# mimic1568_DtoA.net
KiCad netlist of a schematic drawn in EAGLE
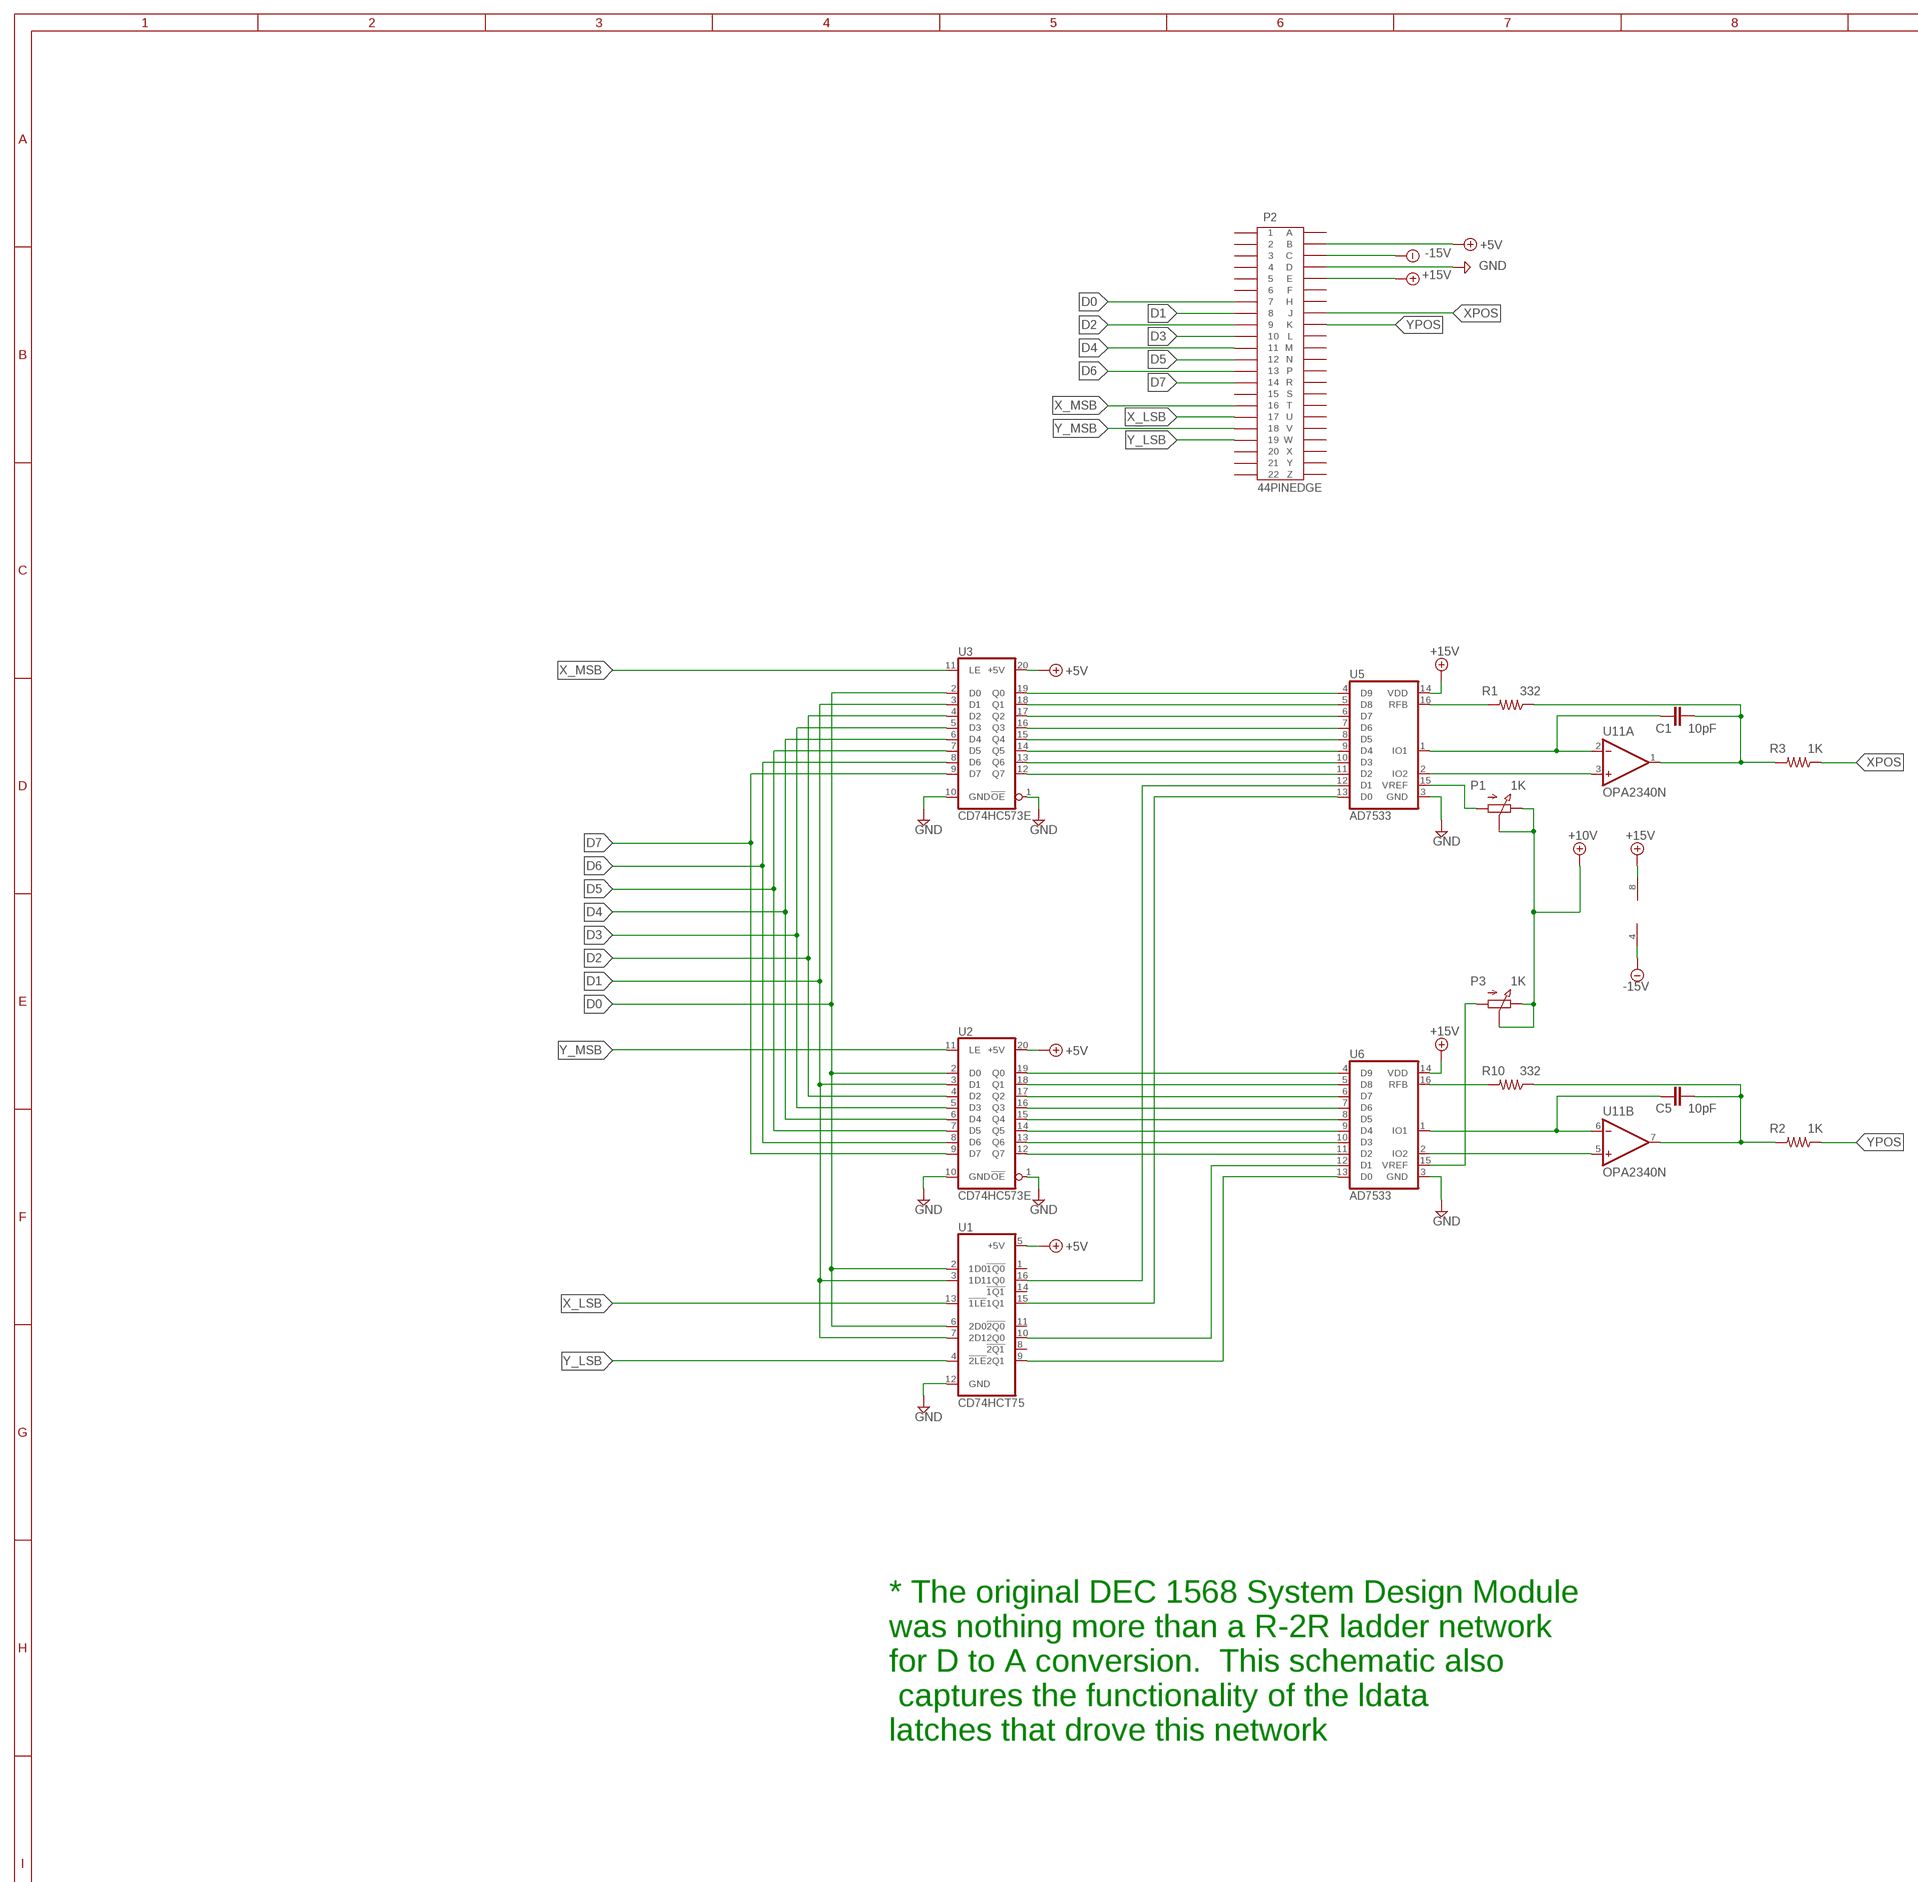
[diagram p0: schematic, sheet 1, part 1 of 2]
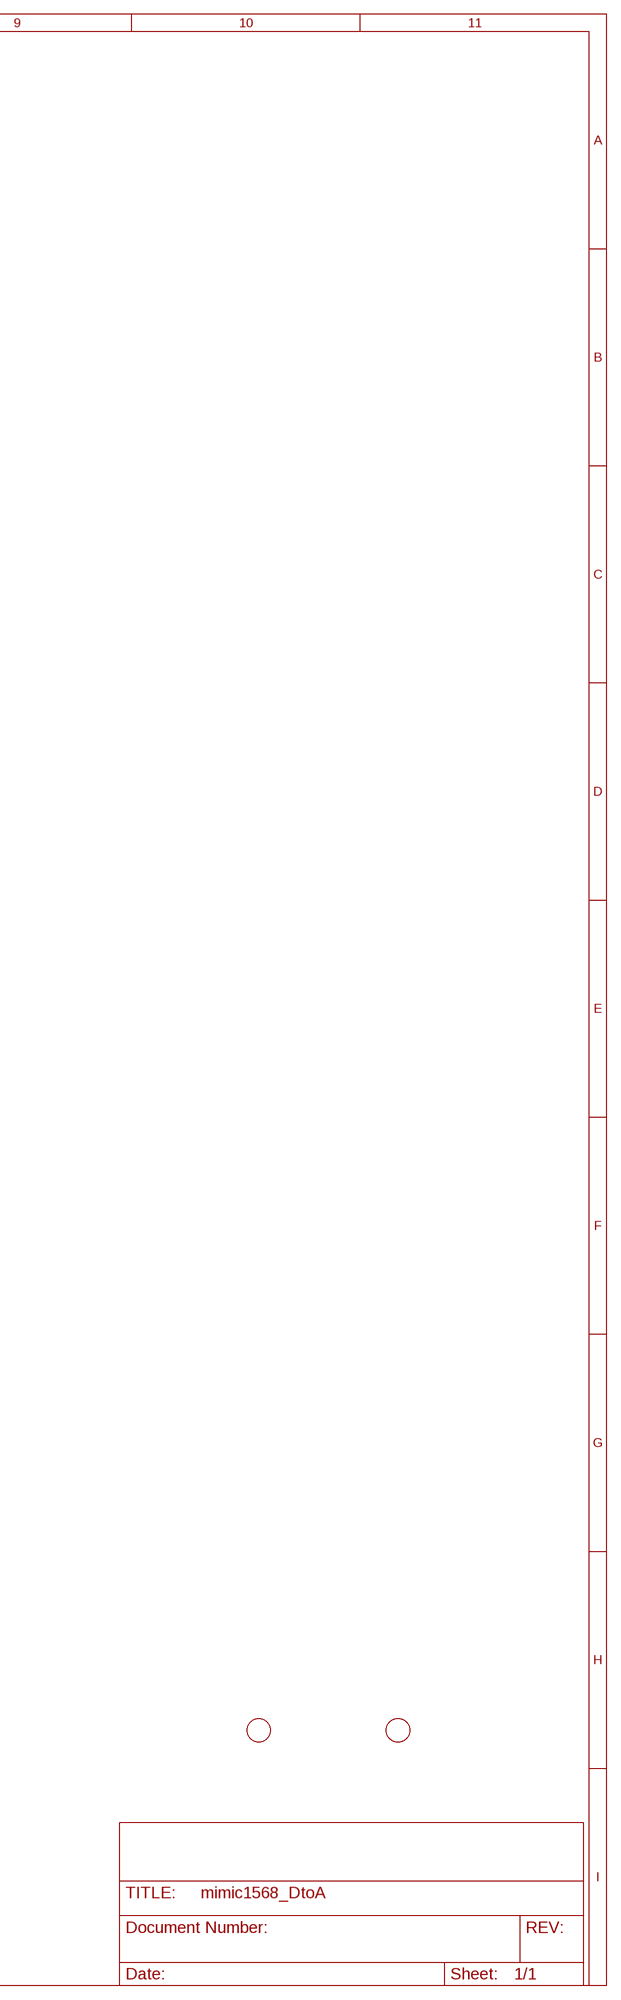
[diagram p1: schematic, sheet 1, part 2 of 2]

(export (version "E")
  (design (tool "Eeschema 10.0.6"))
  (components
    (comp (ref "C1")
      (value "10pF")
      (footprint "eagle-import:C2.5")
      (libsource (lib "eagle-import") (part "C-0.1"))
    )
    (comp (ref "C5")
      (value "10pF")
      (footprint "eagle-import:C2.5")
      (libsource (lib "eagle-import") (part "C-0.1"))
    )
    (comp (ref "P1")
      (value "1K")
      (footprint "eagle-import:3006P")
      (libsource (lib "eagle-import") (part "POT-3006P"))
    )
    (comp (ref "P2")
      (value "44PINEDGE")
      (footprint "eagle-import:44PINEDGE")
      (libsource (lib "eagle-import") (part "44PINEDGE"))
    )
    (comp (ref "P3")
      (value "1K")
      (footprint "eagle-import:3006P")
      (libsource (lib "eagle-import") (part "POT-3006P"))
    )
    (comp (ref "R1")
      (value "332")
      (footprint "eagle-import:0207_10")
      (libsource (lib "eagle-import") (part "R-1/4WATT"))
    )
    (comp (ref "R2")
      (value "1K")
      (footprint "eagle-import:0207_10")
      (libsource (lib "eagle-import") (part "R-1/4WATT"))
    )
    (comp (ref "R3")
      (value "1K")
      (footprint "eagle-import:0207_10")
      (libsource (lib "eagle-import") (part "R-1/4WATT"))
    )
    (comp (ref "R10")
      (value "332")
      (footprint "eagle-import:0207_10")
      (libsource (lib "eagle-import") (part "R-1/4WATT"))
    )
    (comp (ref "U$1")
      (value "FIDUCIAL")
      (footprint "eagle-import:FIDUCIAL_1MM")
      (libsource (lib "eagle-import") (part "FIDUCIAL"))
    )
    (comp (ref "U$2")
      (value "FIDUCIAL")
      (footprint "eagle-import:FIDUCIAL_1MM")
      (libsource (lib "eagle-import") (part "FIDUCIAL"))
    )
    (comp (ref "U1")
      (value "CD74HCT75")
      (footprint "eagle-import:DIP-16")
      (libsource (lib "eagle-import") (part "CD74HCT75"))
    )
    (comp (ref "U2")
      (value "CD74HC573E")
      (footprint "eagle-import:DIP-20")
      (libsource (lib "eagle-import") (part "CD74HC573E"))
    )
    (comp (ref "U3")
      (value "CD74HC573E")
      (footprint "eagle-import:DIP-20")
      (libsource (lib "eagle-import") (part "CD74HC573E"))
    )
    (comp (ref "U5")
      (value "AD7533")
      (footprint "eagle-import:DIP-16")
      (libsource (lib "eagle-import") (part "AD7533"))
    )
    (comp (ref "U6")
      (value "AD7533")
      (footprint "eagle-import:DIP-16")
      (libsource (lib "eagle-import") (part "AD7533"))
    )
    (comp (ref "U11")
      (value "OPA2340N")
      (footprint "eagle-import:DIP-08")
      (fields (field (name "PN") "OPA2340PA"))
      (libsource (lib "eagle-import") (part "OPA2340N"))
    )
  )
  (nets
    (net (code "1") (name "+5V") (class "Default")
      (node (ref "P2") (pin "B") (pinfunction "B_B") (pintype "passive"))
      (node (ref "U1") (pin "5") (pinfunction "+5V_5") (pintype "power_in"))
      (node (ref "U2") (pin "20") (pinfunction "+5V_20") (pintype "power_in"))
      (node (ref "U3") (pin "20") (pinfunction "+5V_20") (pintype "power_in"))
    )
    (net (code "2") (name "+10V") (class "Default")
      (node (ref "P1") (pin "2") (pinfunction "S_2") (pintype "passive"))
      (node (ref "P1") (pin "3") (pinfunction "E_3") (pintype "passive"))
      (node (ref "P3") (pin "2") (pinfunction "S_2") (pintype "passive"))
      (node (ref "P3") (pin "3") (pinfunction "E_3") (pintype "passive"))
    )
    (net (code "3") (name "+15V") (class "Default")
      (node (ref "P2") (pin "E") (pinfunction "E_E") (pintype "passive"))
      (node (ref "U11") (pin "8") (pinfunction "V+_8") (pintype "power_in"))
      (node (ref "U5") (pin "14") (pinfunction "VDD_14") (pintype "power_in"))
      (node (ref "U6") (pin "14") (pinfunction "VDD_14") (pintype "power_in"))
    )
    (net (code "4") (name "-15V") (class "Default")
      (node (ref "P2") (pin "C") (pinfunction "C_C") (pintype "passive"))
      (node (ref "U11") (pin "4") (pinfunction "V-_4") (pintype "power_in"))
    )
    (net (code "5") (name "D0") (class "Default")
      (node (ref "P2") (pin "7") (pinfunction "7_7") (pintype "passive"))
      (node (ref "U1") (pin "2") (pinfunction "1D0_2") (pintype "input"))
      (node (ref "U1") (pin "6") (pinfunction "2D0_6") (pintype "input"))
      (node (ref "U2") (pin "2") (pinfunction "D0_2") (pintype "input"))
      (node (ref "U3") (pin "2") (pinfunction "D0_2") (pintype "input"))
    )
    (net (code "6") (name "D1") (class "Default")
      (node (ref "P2") (pin "8") (pinfunction "8_8") (pintype "passive"))
      (node (ref "U1") (pin "3") (pinfunction "1D1_3") (pintype "input"))
      (node (ref "U1") (pin "7") (pinfunction "2D1_7") (pintype "input"))
      (node (ref "U2") (pin "3") (pinfunction "D1_3") (pintype "input"))
      (node (ref "U3") (pin "3") (pinfunction "D1_3") (pintype "input"))
    )
    (net (code "7") (name "D2") (class "Default")
      (node (ref "P2") (pin "9") (pinfunction "9_9") (pintype "passive"))
      (node (ref "U2") (pin "4") (pinfunction "D2_4") (pintype "input"))
      (node (ref "U3") (pin "4") (pinfunction "D2_4") (pintype "input"))
    )
    (net (code "8") (name "D3") (class "Default")
      (node (ref "P2") (pin "10") (pinfunction "10_10") (pintype "passive"))
      (node (ref "U2") (pin "5") (pinfunction "D3_5") (pintype "input"))
      (node (ref "U3") (pin "5") (pinfunction "D3_5") (pintype "input"))
    )
    (net (code "9") (name "D4") (class "Default")
      (node (ref "P2") (pin "11") (pinfunction "11_11") (pintype "passive"))
      (node (ref "U2") (pin "6") (pinfunction "D4_6") (pintype "input"))
      (node (ref "U3") (pin "6") (pinfunction "D4_6") (pintype "input"))
    )
    (net (code "10") (name "D5") (class "Default")
      (node (ref "P2") (pin "12") (pinfunction "12_12") (pintype "passive"))
      (node (ref "U2") (pin "7") (pinfunction "D5_7") (pintype "input"))
      (node (ref "U3") (pin "7") (pinfunction "D5_7") (pintype "input"))
    )
    (net (code "11") (name "D6") (class "Default")
      (node (ref "P2") (pin "13") (pinfunction "13_13") (pintype "passive"))
      (node (ref "U2") (pin "8") (pinfunction "D6_8") (pintype "input"))
      (node (ref "U3") (pin "8") (pinfunction "D6_8") (pintype "input"))
    )
    (net (code "12") (name "D7") (class "Default")
      (node (ref "P2") (pin "14") (pinfunction "14_14") (pintype "passive"))
      (node (ref "U2") (pin "9") (pinfunction "D7_9") (pintype "input"))
      (node (ref "U3") (pin "9") (pinfunction "D7_9") (pintype "input"))
    )
    (net (code "13") (name "GND") (class "Default")
      (node (ref "P2") (pin "D") (pinfunction "D_D") (pintype "passive"))
      (node (ref "U1") (pin "12") (pinfunction "GND_12") (pintype "power_in"))
      (node (ref "U2") (pin "1") (pinfunction "~{OE}_1") (pintype "input"))
      (node (ref "U2") (pin "10") (pinfunction "GND_10") (pintype "power_in"))
      (node (ref "U3") (pin "1") (pinfunction "~{OE}_1") (pintype "input"))
      (node (ref "U3") (pin "10") (pinfunction "GND_10") (pintype "power_in"))
      (node (ref "U5") (pin "3") (pinfunction "GND_3") (pintype "power_in"))
      (node (ref "U6") (pin "3") (pinfunction "GND_3") (pintype "power_in"))
    )
    (net (code "14") (name "Net-(P1-A)") (class "Default")
      (node (ref "P1") (pin "1") (pinfunction "A_1") (pintype "passive"))
      (node (ref "U5") (pin "15") (pinfunction "VREF_15") (pintype "power_in"))
    )
    (net (code "15") (name "Net-(P3-A)") (class "Default")
      (node (ref "P3") (pin "1") (pinfunction "A_1") (pintype "passive"))
      (node (ref "U6") (pin "15") (pinfunction "VREF_15") (pintype "power_in"))
    )
    (net (code "16") (name "Net-(R1-P$1)") (class "Default")
      (node (ref "C1") (pin "2") (pinfunction "2_2") (pintype "passive"))
      (node (ref "R1") (pin "1") (pinfunction "P$1_1") (pintype "passive"))
      (node (ref "R3") (pin "2") (pinfunction "P$2_2") (pintype "passive"))
      (node (ref "U11") (pin "1") (pinfunction "OUT_1") (pintype "output"))
    )
    (net (code "17") (name "Net-(R1-P$2)") (class "Default")
      (node (ref "R1") (pin "2") (pinfunction "P$2_2") (pintype "passive"))
      (node (ref "U5") (pin "16") (pinfunction "RFB_16") (pintype "input"))
    )
    (net (code "18") (name "Net-(R10-P$1)") (class "Default")
      (node (ref "C5") (pin "2") (pinfunction "2_2") (pintype "passive"))
      (node (ref "R10") (pin "1") (pinfunction "P$1_1") (pintype "passive"))
      (node (ref "R2") (pin "2") (pinfunction "P$2_2") (pintype "passive"))
      (node (ref "U11") (pin "7") (pinfunction "OUT_7") (pintype "output"))
    )
    (net (code "19") (name "Net-(R10-P$2)") (class "Default")
      (node (ref "R10") (pin "2") (pinfunction "P$2_2") (pintype "passive"))
      (node (ref "U6") (pin "16") (pinfunction "RFB_16") (pintype "input"))
    )
    (net (code "20") (name "Net-(U1-1Q0)") (class "Default")
      (node (ref "U1") (pin "16") (pinfunction "1Q0_16") (pintype "output"))
      (node (ref "U5") (pin "12") (pinfunction "D1_12") (pintype "input"))
    )
    (net (code "21") (name "Net-(U1-1Q1)") (class "Default")
      (node (ref "U1") (pin "15") (pinfunction "1Q1_15") (pintype "output"))
      (node (ref "U5") (pin "13") (pinfunction "D0_13") (pintype "input"))
    )
    (net (code "22") (name "Net-(U1-2Q0)") (class "Default")
      (node (ref "U1") (pin "10") (pinfunction "2Q0_10") (pintype "output"))
      (node (ref "U6") (pin "12") (pinfunction "D1_12") (pintype "input"))
    )
    (net (code "23") (name "Net-(U1-2Q1)") (class "Default")
      (node (ref "U1") (pin "9") (pinfunction "2Q1_9") (pintype "output"))
      (node (ref "U6") (pin "13") (pinfunction "D0_13") (pintype "input"))
    )
    (net (code "24") (name "Net-(U2-Q0)") (class "Default")
      (node (ref "U2") (pin "19") (pinfunction "Q0_19") (pintype "tri_state"))
      (node (ref "U6") (pin "4") (pinfunction "D9_4") (pintype "input"))
    )
    (net (code "25") (name "Net-(U2-Q1)") (class "Default")
      (node (ref "U2") (pin "18") (pinfunction "Q1_18") (pintype "tri_state"))
      (node (ref "U6") (pin "5") (pinfunction "D8_5") (pintype "input"))
    )
    (net (code "26") (name "Net-(U2-Q2)") (class "Default")
      (node (ref "U2") (pin "17") (pinfunction "Q2_17") (pintype "tri_state"))
      (node (ref "U6") (pin "6") (pinfunction "D7_6") (pintype "input"))
    )
    (net (code "27") (name "Net-(U2-Q3)") (class "Default")
      (node (ref "U2") (pin "16") (pinfunction "Q3_16") (pintype "tri_state"))
      (node (ref "U6") (pin "7") (pinfunction "D6_7") (pintype "input"))
    )
    (net (code "28") (name "Net-(U2-Q4)") (class "Default")
      (node (ref "U2") (pin "15") (pinfunction "Q4_15") (pintype "tri_state"))
      (node (ref "U6") (pin "8") (pinfunction "D5_8") (pintype "input"))
    )
    (net (code "29") (name "Net-(U2-Q5)") (class "Default")
      (node (ref "U2") (pin "14") (pinfunction "Q5_14") (pintype "tri_state"))
      (node (ref "U6") (pin "9") (pinfunction "D4_9") (pintype "input"))
    )
    (net (code "30") (name "Net-(U2-Q6)") (class "Default")
      (node (ref "U2") (pin "13") (pinfunction "Q6_13") (pintype "tri_state"))
      (node (ref "U6") (pin "10") (pinfunction "D3_10") (pintype "input"))
    )
    (net (code "31") (name "Net-(U2-Q7)") (class "Default")
      (node (ref "U2") (pin "12") (pinfunction "Q7_12") (pintype "tri_state"))
      (node (ref "U6") (pin "11") (pinfunction "D2_11") (pintype "input"))
    )
    (net (code "32") (name "Net-(U3-Q0)") (class "Default")
      (node (ref "U3") (pin "19") (pinfunction "Q0_19") (pintype "tri_state"))
      (node (ref "U5") (pin "4") (pinfunction "D9_4") (pintype "input"))
    )
    (net (code "33") (name "Net-(U3-Q1)") (class "Default")
      (node (ref "U3") (pin "18") (pinfunction "Q1_18") (pintype "tri_state"))
      (node (ref "U5") (pin "5") (pinfunction "D8_5") (pintype "input"))
    )
    (net (code "34") (name "Net-(U3-Q2)") (class "Default")
      (node (ref "U3") (pin "17") (pinfunction "Q2_17") (pintype "tri_state"))
      (node (ref "U5") (pin "6") (pinfunction "D7_6") (pintype "input"))
    )
    (net (code "35") (name "Net-(U3-Q3)") (class "Default")
      (node (ref "U3") (pin "16") (pinfunction "Q3_16") (pintype "tri_state"))
      (node (ref "U5") (pin "7") (pinfunction "D6_7") (pintype "input"))
    )
    (net (code "36") (name "Net-(U3-Q4)") (class "Default")
      (node (ref "U3") (pin "15") (pinfunction "Q4_15") (pintype "tri_state"))
      (node (ref "U5") (pin "8") (pinfunction "D5_8") (pintype "input"))
    )
    (net (code "37") (name "Net-(U3-Q5)") (class "Default")
      (node (ref "U3") (pin "14") (pinfunction "Q5_14") (pintype "tri_state"))
      (node (ref "U5") (pin "9") (pinfunction "D4_9") (pintype "input"))
    )
    (net (code "38") (name "Net-(U3-Q6)") (class "Default")
      (node (ref "U3") (pin "13") (pinfunction "Q6_13") (pintype "tri_state"))
      (node (ref "U5") (pin "10") (pinfunction "D3_10") (pintype "input"))
    )
    (net (code "39") (name "Net-(U3-Q7)") (class "Default")
      (node (ref "U3") (pin "12") (pinfunction "Q7_12") (pintype "tri_state"))
      (node (ref "U5") (pin "11") (pinfunction "D2_11") (pintype "input"))
    )
    (net (code "40") (name "Net-(U11A-+IN)") (class "Default")
      (node (ref "U11") (pin "3") (pinfunction "+IN_3") (pintype "input"))
      (node (ref "U5") (pin "2") (pinfunction "IO2_2") (pintype "output"))
    )
    (net (code "41") (name "Net-(U11A--IN)") (class "Default")
      (node (ref "C1") (pin "1") (pinfunction "1_1") (pintype "passive"))
      (node (ref "U11") (pin "2") (pinfunction "-IN_2") (pintype "input"))
      (node (ref "U5") (pin "1") (pinfunction "IO1_1") (pintype "output"))
    )
    (net (code "42") (name "Net-(U11B-+IN)") (class "Default")
      (node (ref "U11") (pin "5") (pinfunction "+IN_5") (pintype "input"))
      (node (ref "U6") (pin "2") (pinfunction "IO2_2") (pintype "output"))
    )
    (net (code "43") (name "Net-(U11B--IN)") (class "Default")
      (node (ref "C5") (pin "1") (pinfunction "1_1") (pintype "passive"))
      (node (ref "U11") (pin "6") (pinfunction "-IN_6") (pintype "input"))
      (node (ref "U6") (pin "1") (pinfunction "IO1_1") (pintype "output"))
    )
    (net (code "44") (name "XPOS") (class "Default")
      (node (ref "P2") (pin "J") (pinfunction "J_J") (pintype "passive"))
      (node (ref "R3") (pin "1") (pinfunction "P$1_1") (pintype "passive"))
    )
    (net (code "45") (name "X_LSB") (class "Default")
      (node (ref "P2") (pin "17") (pinfunction "17_17") (pintype "passive"))
      (node (ref "U1") (pin "13") (pinfunction "~{1LE}_13") (pintype "input"))
    )
    (net (code "46") (name "X_MSB") (class "Default")
      (node (ref "P2") (pin "16") (pinfunction "16_16") (pintype "passive"))
      (node (ref "U3") (pin "11") (pinfunction "LE_11") (pintype "input"))
    )
    (net (code "47") (name "YPOS") (class "Default")
      (node (ref "P2") (pin "K") (pinfunction "K_K") (pintype "passive"))
      (node (ref "R2") (pin "1") (pinfunction "P$1_1") (pintype "passive"))
    )
    (net (code "48") (name "Y_LSB") (class "Default")
      (node (ref "P2") (pin "19") (pinfunction "19_19") (pintype "passive"))
      (node (ref "U1") (pin "4") (pinfunction "~{2LE}_4") (pintype "input"))
    )
    (net (code "49") (name "Y_MSB") (class "Default")
      (node (ref "P2") (pin "18") (pinfunction "18_18") (pintype "passive"))
      (node (ref "U2") (pin "11") (pinfunction "LE_11") (pintype "input"))
    )
    (net (code "50") (name "unconnected-(P2-Pad1)") (class "Default")
      (node (ref "P2") (pin "1") (pinfunction "1_1") (pintype "passive"))
    )
    (net (code "51") (name "unconnected-(P2-Pad2)") (class "Default")
      (node (ref "P2") (pin "2") (pinfunction "2_2") (pintype "passive"))
    )
    (net (code "52") (name "unconnected-(P2-Pad3)") (class "Default")
      (node (ref "P2") (pin "3") (pinfunction "3_3") (pintype "passive"))
    )
    (net (code "53") (name "unconnected-(P2-Pad4)") (class "Default")
      (node (ref "P2") (pin "4") (pinfunction "4_4") (pintype "passive"))
    )
    (net (code "54") (name "unconnected-(P2-Pad5)") (class "Default")
      (node (ref "P2") (pin "5") (pinfunction "5_5") (pintype "passive"))
    )
    (net (code "55") (name "unconnected-(P2-Pad6)") (class "Default")
      (node (ref "P2") (pin "6") (pinfunction "6_6") (pintype "passive"))
    )
    (net (code "56") (name "unconnected-(P2-Pad15)") (class "Default")
      (node (ref "P2") (pin "15") (pinfunction "15_15") (pintype "passive"))
    )
    (net (code "57") (name "unconnected-(P2-Pad20)") (class "Default")
      (node (ref "P2") (pin "20") (pinfunction "20_20") (pintype "passive"))
    )
    (net (code "58") (name "unconnected-(P2-Pad21)") (class "Default")
      (node (ref "P2") (pin "21") (pinfunction "21_21") (pintype "passive"))
    )
    (net (code "59") (name "unconnected-(P2-Pad22)") (class "Default")
      (node (ref "P2") (pin "22") (pinfunction "22_22") (pintype "passive"))
    )
    (net (code "60") (name "unconnected-(P2-PadA)") (class "Default")
      (node (ref "P2") (pin "A") (pinfunction "A_A") (pintype "passive"))
    )
    (net (code "61") (name "unconnected-(P2-PadF)") (class "Default")
      (node (ref "P2") (pin "F") (pinfunction "F_F") (pintype "passive"))
    )
    (net (code "62") (name "unconnected-(P2-PadH)") (class "Default")
      (node (ref "P2") (pin "H") (pinfunction "H_H") (pintype "passive"))
    )
    (net (code "63") (name "unconnected-(P2-PadL)") (class "Default")
      (node (ref "P2") (pin "L") (pinfunction "L_L") (pintype "passive"))
    )
    (net (code "64") (name "unconnected-(P2-PadM)") (class "Default")
      (node (ref "P2") (pin "M") (pinfunction "M_M") (pintype "passive"))
    )
    (net (code "65") (name "unconnected-(P2-PadN)") (class "Default")
      (node (ref "P2") (pin "N") (pinfunction "N_N") (pintype "passive"))
    )
    (net (code "66") (name "unconnected-(P2-PadP)") (class "Default")
      (node (ref "P2") (pin "P") (pinfunction "P_P") (pintype "passive"))
    )
    (net (code "67") (name "unconnected-(P2-PadR)") (class "Default")
      (node (ref "P2") (pin "R") (pinfunction "R_R") (pintype "passive"))
    )
    (net (code "68") (name "unconnected-(P2-PadS)") (class "Default")
      (node (ref "P2") (pin "S") (pinfunction "S_S") (pintype "passive"))
    )
    (net (code "69") (name "unconnected-(P2-PadT)") (class "Default")
      (node (ref "P2") (pin "T") (pinfunction "T_T") (pintype "passive"))
    )
    (net (code "70") (name "unconnected-(P2-PadU)") (class "Default")
      (node (ref "P2") (pin "U") (pinfunction "U_U") (pintype "passive"))
    )
    (net (code "71") (name "unconnected-(P2-PadV)") (class "Default")
      (node (ref "P2") (pin "V") (pinfunction "V_V") (pintype "passive"))
    )
    (net (code "72") (name "unconnected-(P2-PadW)") (class "Default")
      (node (ref "P2") (pin "W") (pinfunction "W_W") (pintype "passive"))
    )
    (net (code "73") (name "unconnected-(P2-PadX)") (class "Default")
      (node (ref "P2") (pin "X") (pinfunction "X_X") (pintype "passive"))
    )
    (net (code "74") (name "unconnected-(P2-PadY)") (class "Default")
      (node (ref "P2") (pin "Y") (pinfunction "Y_Y") (pintype "passive"))
    )
    (net (code "75") (name "unconnected-(P2-PadZ)") (class "Default")
      (node (ref "P2") (pin "Z") (pinfunction "Z_Z") (pintype "passive"))
    )
    (net (code "76") (name "unconnected-(U1-~{1Q0}-Pad1)") (class "Default")
      (node (ref "U1") (pin "1") (pinfunction "~{1Q0}_1") (pintype "output"))
    )
    (net (code "77") (name "unconnected-(U1-~{1Q1}-Pad14)") (class "Default")
      (node (ref "U1") (pin "14") (pinfunction "~{1Q1}_14") (pintype "output"))
    )
    (net (code "78") (name "unconnected-(U1-~{2Q0}-Pad11)") (class "Default")
      (node (ref "U1") (pin "11") (pinfunction "~{2Q0}_11") (pintype "output"))
    )
    (net (code "79") (name "unconnected-(U1-~{2Q1}-Pad8)") (class "Default")
      (node (ref "U1") (pin "8") (pinfunction "~{2Q1}_8") (pintype "output"))
    )
  )
)
